# Blinky.net
KiCad netlist of a schematic drawn in EAGLE
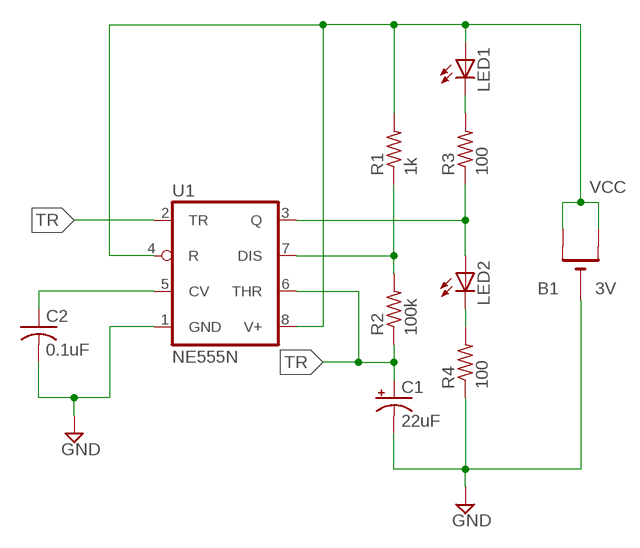
[diagram p0: schematic, sheet 1]

(export (version "E")
  (design (tool "Eeschema 10.0.6"))
  (components
    (comp (ref "B1")
      (value "3V")
      (footprint "eagle-import:CR1220-THM")
      (fields (field (name "SPICEPREFIX") "J"))
      (libsource (lib "eagle-import") (part "CR1220THM"))
    )
    (comp (ref "C1")
      (value "22uF")
      (footprint "eagle-import:E1,8-4")
      (libsource (lib "eagle-import") (part "CPOL-USE1.8-4"))
    )
    (comp (ref "C2")
      (value "0.1uF")
      (footprint "eagle-import:C025-025X050")
      (libsource (lib "eagle-import") (part "C-US025-025X050"))
    )
    (comp (ref "LED1")
      (value "LED5MM")
      (footprint "eagle-import:LED5MM")
      (libsource (lib "eagle-import") (part "LED5MM"))
    )
    (comp (ref "LED2")
      (value "LED5MM")
      (footprint "eagle-import:LED5MM")
      (libsource (lib "eagle-import") (part "LED5MM"))
    )
    (comp (ref "R1")
      (value "1k")
      (footprint "eagle-import:0309_12")
      (libsource (lib "eagle-import") (part "R-US_0309/12"))
    )
    (comp (ref "R2")
      (value "100k")
      (footprint "eagle-import:0309_12")
      (libsource (lib "eagle-import") (part "R-US_0309/12"))
    )
    (comp (ref "R3")
      (value "100")
      (footprint "eagle-import:0309_12")
      (libsource (lib "eagle-import") (part "R-US_0309/12"))
    )
    (comp (ref "R4")
      (value "100")
      (footprint "eagle-import:0309_12")
      (libsource (lib "eagle-import") (part "R-US_0309/12"))
    )
    (comp (ref "U1")
      (value "NE555N")
      (footprint "eagle-import:DIL08")
      (fields (field (name "SPICEPREFIX") "X"))
      (libsource (lib "eagle-import") (part "555NNE"))
    )
  )
  (nets
    (net (code "1") (name "/VCC") (class "Default")
      (node (ref "B1") (pin "+1") (pinfunction "+_+1") (pintype "passive"))
      (node (ref "B1") (pin "+2") (pinfunction "+1_+2") (pintype "passive"))
      (node (ref "LED1") (pin "A") (pinfunction "A_A") (pintype "passive"))
      (node (ref "R1") (pin "2") (pinfunction "2_2") (pintype "passive"))
      (node (ref "U1") (pin "4") (pinfunction "R_4") (pintype "input"))
      (node (ref "U1") (pin "8") (pinfunction "V+_8") (pintype "power_in"))
    )
    (net (code "2") (name "GND") (class "Default")
      (node (ref "B1") (pin "-") (pinfunction "-_-") (pintype "passive"))
      (node (ref "C1") (pin "-") (pinfunction "-_-") (pintype "passive"))
      (node (ref "C2") (pin "2") (pinfunction "2_2") (pintype "passive"))
      (node (ref "R4") (pin "1") (pinfunction "1_1") (pintype "passive"))
      (node (ref "U1") (pin "1") (pinfunction "GND_1") (pintype "power_in"))
    )
    (net (code "3") (name "Net-(LED1-C)") (class "Default")
      (node (ref "LED1") (pin "K") (pinfunction "C_K") (pintype "passive"))
      (node (ref "R3") (pin "2") (pinfunction "2_2") (pintype "passive"))
    )
    (net (code "4") (name "Net-(LED2-C)") (class "Default")
      (node (ref "LED2") (pin "K") (pinfunction "C_K") (pintype "passive"))
      (node (ref "R4") (pin "2") (pinfunction "2_2") (pintype "passive"))
    )
    (net (code "5") (name "Net-(U1-CV)") (class "Default")
      (node (ref "C2") (pin "1") (pinfunction "1_1") (pintype "passive"))
      (node (ref "U1") (pin "5") (pinfunction "CV_5") (pintype "input"))
    )
    (net (code "6") (name "Net-(U1-DIS)") (class "Default")
      (node (ref "R1") (pin "1") (pinfunction "1_1") (pintype "passive"))
      (node (ref "R2") (pin "2") (pinfunction "2_2") (pintype "passive"))
      (node (ref "U1") (pin "7") (pinfunction "DIS_7") (pintype "input"))
    )
    (net (code "7") (name "Net-(U1-Q)") (class "Default")
      (node (ref "LED2") (pin "A") (pinfunction "A_A") (pintype "passive"))
      (node (ref "R3") (pin "1") (pinfunction "1_1") (pintype "passive"))
      (node (ref "U1") (pin "3") (pinfunction "Q_3") (pintype "output"))
    )
    (net (code "8") (name "TR") (class "Default")
      (node (ref "C1") (pin "+") (pinfunction "+_+") (pintype "passive"))
      (node (ref "R2") (pin "1") (pinfunction "1_1") (pintype "passive"))
      (node (ref "U1") (pin "2") (pinfunction "TR_2") (pintype "input"))
      (node (ref "U1") (pin "6") (pinfunction "THR_6") (pintype "input"))
    )
  )
)
